# power_control.net
KiCad netlist of a schematic drawn in EAGLE
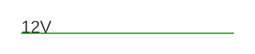
[diagram p0: schematic, sheet 1]
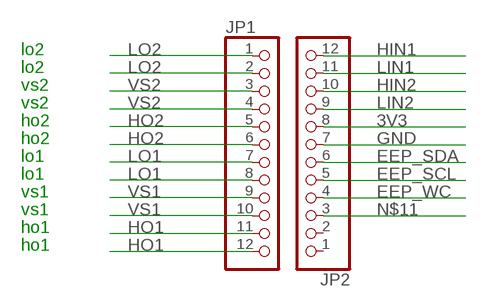
[diagram p1: schematic, sheet 2]
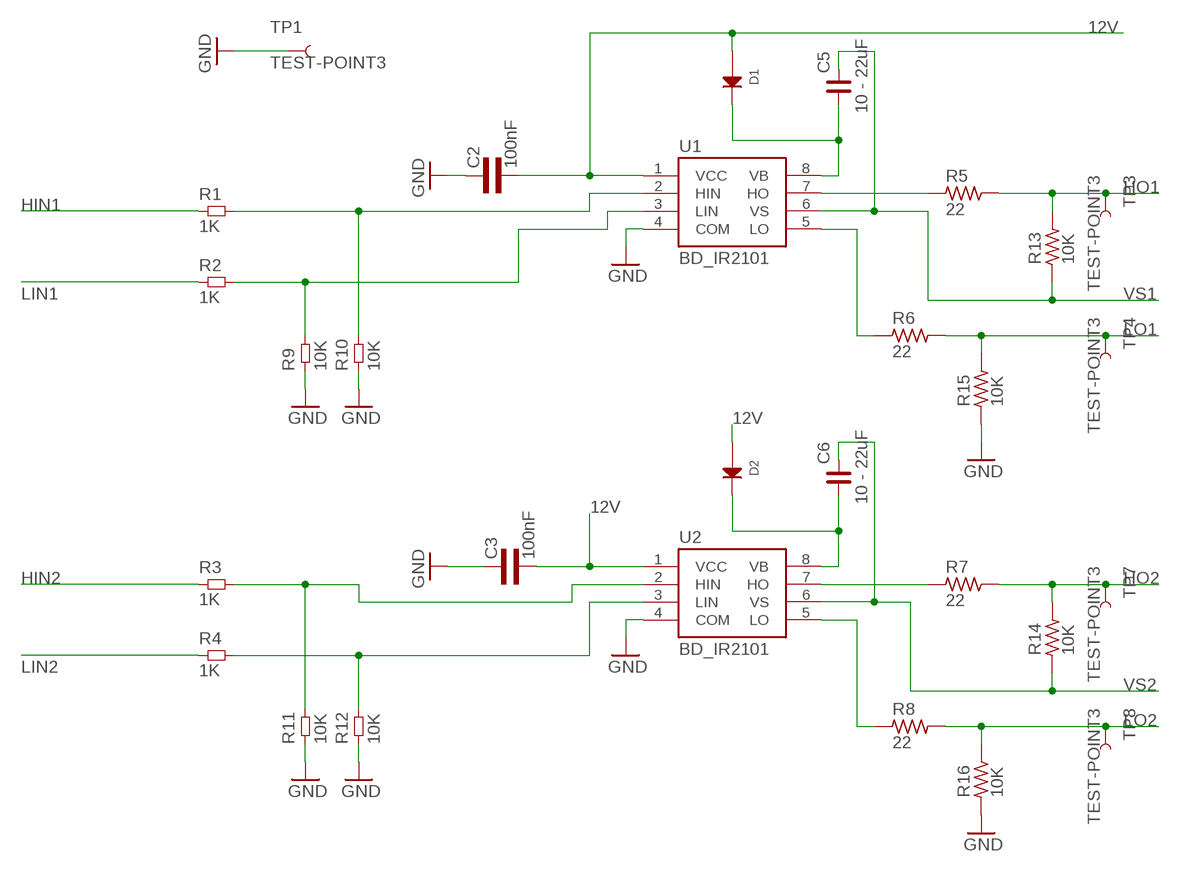
[diagram p2: schematic, sheet 3]
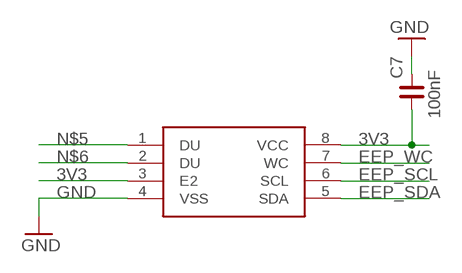
[diagram p3: schematic, sheet 4]
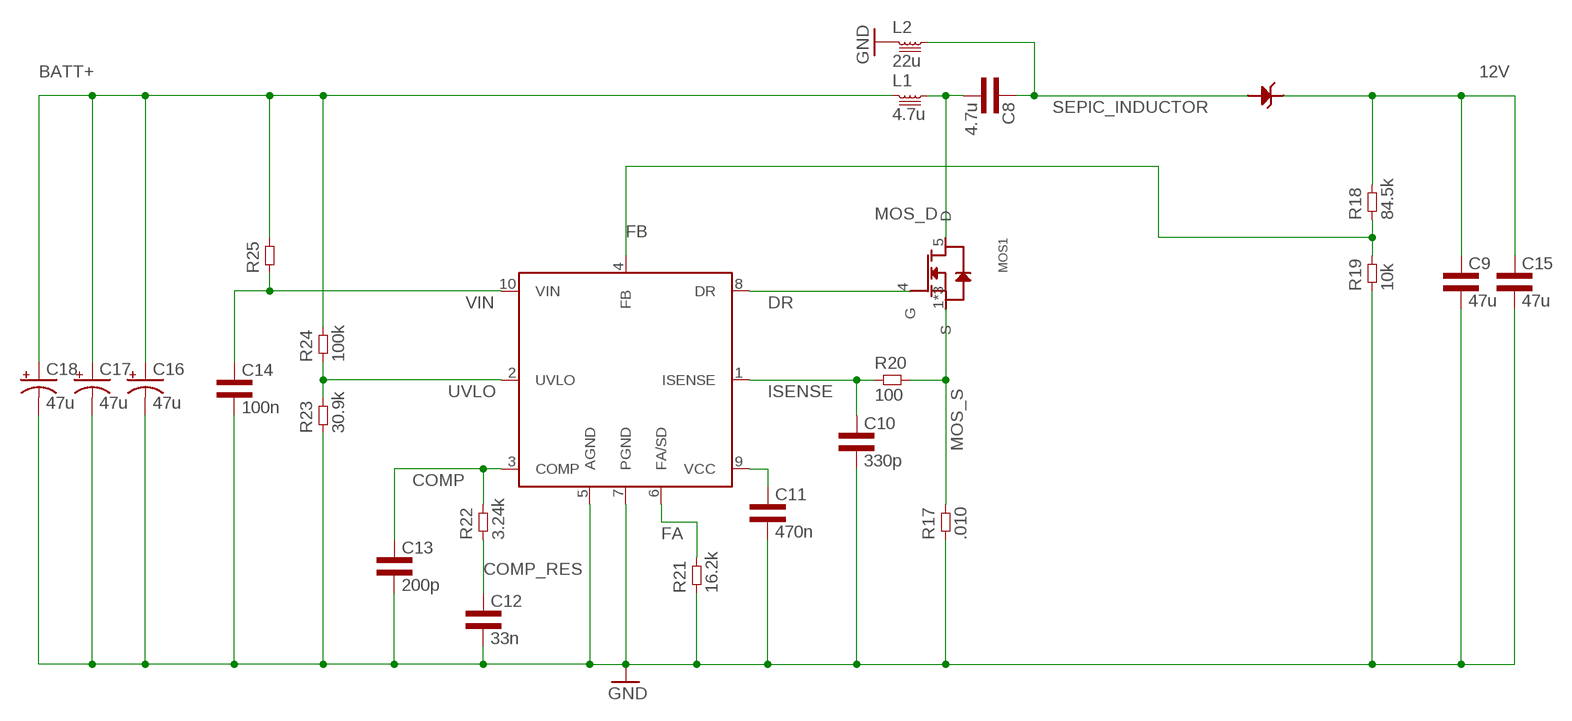
[diagram p4: schematic, sheet 5]

(export (version "E")
  (design (tool "Eeschema 10.0.6"))
  (components
    (comp (ref "JP1")
      (value "PINHD-1X12_2.54-SMD")
      (footprint "eagle-import:1X12SMD")
      (libsource (lib "eagle-import") (part "PINHD-1X12_2.54-SMD"))
    )
    (comp (ref "JP2")
      (value "PINHD-1X12_2.54-SMD")
      (footprint "eagle-import:1X12SMD")
      (libsource (lib "eagle-import") (part "PINHD-1X12_2.54-SMD"))
    )
    (comp (ref "C2")
      (value "100nF")
      (footprint "eagle-import:0603L3")
      (libsource (lib "eagle-import") (part "CAP0603L3"))
    )
    (comp (ref "C3")
      (value "100nF")
      (footprint "eagle-import:0603L3")
      (libsource (lib "eagle-import") (part "CAP0603L3"))
    )
    (comp (ref "C5")
      (value "10 - 22uF")
      (footprint "eagle-import:C0805")
      (libsource (lib "eagle-import") (part "C_0805"))
    )
    (comp (ref "C6")
      (value "10 - 22uF")
      (footprint "eagle-import:C0805")
      (libsource (lib "eagle-import") (part "C_0805"))
    )
    (comp (ref "D1")
      (value "DIODETMINIP2-F2-B")
      (footprint "eagle-import:TMINIP2-F2-B")
      (fields (field (name "PARTNUM") "DB2441600L"))
      (libsource (lib "eagle-import") (part "DIODETMINIP2-F2-B"))
    )
    (comp (ref "D2")
      (value "DIODETMINIP2-F2-B")
      (footprint "eagle-import:TMINIP2-F2-B")
      (fields (field (name "PARTNUM") "DB2441600L"))
      (libsource (lib "eagle-import") (part "DIODETMINIP2-F2-B"))
    )
    (comp (ref "R1")
      (value "1K")
      (footprint "eagle-import:0603L3")
      (libsource (lib "eagle-import") (part "RES0603L3"))
    )
    (comp (ref "R2")
      (value "1K")
      (footprint "eagle-import:0603L3")
      (libsource (lib "eagle-import") (part "RES0603L3"))
    )
    (comp (ref "R3")
      (value "1K")
      (footprint "eagle-import:0603L3")
      (libsource (lib "eagle-import") (part "RES0603L3"))
    )
    (comp (ref "R4")
      (value "1K")
      (footprint "eagle-import:0603L3")
      (libsource (lib "eagle-import") (part "RES0603L3"))
    )
    (comp (ref "R5")
      (value "22")
      (footprint "eagle-import:R0805")
      (libsource (lib "eagle-import") (part "R_0805"))
    )
    (comp (ref "R6")
      (value "22")
      (footprint "eagle-import:R0805")
      (libsource (lib "eagle-import") (part "R_0805"))
    )
    (comp (ref "R7")
      (value "22")
      (footprint "eagle-import:R0805")
      (libsource (lib "eagle-import") (part "R_0805"))
    )
    (comp (ref "R8")
      (value "22")
      (footprint "eagle-import:R0805")
      (libsource (lib "eagle-import") (part "R_0805"))
    )
    (comp (ref "R9")
      (value "10K")
      (footprint "eagle-import:0603L3")
      (libsource (lib "eagle-import") (part "RES0603L3"))
    )
    (comp (ref "R10")
      (value "10K")
      (footprint "eagle-import:0603L3")
      (libsource (lib "eagle-import") (part "RES0603L3"))
    )
    (comp (ref "R11")
      (value "10K")
      (footprint "eagle-import:0603L3")
      (libsource (lib "eagle-import") (part "RES0603L3"))
    )
    (comp (ref "R12")
      (value "10K")
      (footprint "eagle-import:0603L3")
      (libsource (lib "eagle-import") (part "RES0603L3"))
    )
    (comp (ref "R13")
      (value "10K")
      (footprint "eagle-import:R0805")
      (libsource (lib "eagle-import") (part "R_0805"))
    )
    (comp (ref "R14")
      (value "10K")
      (footprint "eagle-import:R0805")
      (libsource (lib "eagle-import") (part "R_0805"))
    )
    (comp (ref "R15")
      (value "10K")
      (footprint "eagle-import:R0805")
      (libsource (lib "eagle-import") (part "R_0805"))
    )
    (comp (ref "R16")
      (value "10K")
      (footprint "eagle-import:R0805")
      (libsource (lib "eagle-import") (part "R_0805"))
    )
    (comp (ref "TP1")
      (value "TEST-POINT3")
      (footprint "eagle-import:PAD.03X.03")
      (libsource (lib "eagle-import") (part "TEST-POINT3"))
    )
    (comp (ref "TP3")
      (value "TEST-POINT3")
      (footprint "eagle-import:PAD.03X.03")
      (libsource (lib "eagle-import") (part "TEST-POINT3"))
    )
    (comp (ref "TP4")
      (value "TEST-POINT3")
      (footprint "eagle-import:PAD.03X.03")
      (libsource (lib "eagle-import") (part "TEST-POINT3"))
    )
    (comp (ref "TP7")
      (value "TEST-POINT3")
      (footprint "eagle-import:PAD.03X.03")
      (libsource (lib "eagle-import") (part "TEST-POINT3"))
    )
    (comp (ref "TP8")
      (value "TEST-POINT3")
      (footprint "eagle-import:PAD.03X.03")
      (libsource (lib "eagle-import") (part "TEST-POINT3"))
    )
    (comp (ref "U1")
      (value "BD_IR2101")
      (footprint "eagle-import:SO8")
      (libsource (lib "eagle-import") (part "BD_IR2101"))
    )
    (comp (ref "U2")
      (value "BD_IR2101")
      (footprint "eagle-import:SO8")
      (libsource (lib "eagle-import") (part "BD_IR2101"))
    )
    (comp (ref "C8")
      (value "4.7u")
      (footprint "eagle-import:1206L3")
      (libsource (lib "eagle-import") (part "CAP1206L3"))
    )
    (comp (ref "C9")
      (value "47u")
      (footprint "eagle-import:1210L3")
      (libsource (lib "eagle-import") (part "CAP1210L3"))
    )
    (comp (ref "C10")
      (value "330p")
      (footprint "eagle-import:0402L3")
      (libsource (lib "eagle-import") (part "CAP0402L3"))
    )
    (comp (ref "C11")
      (value "470n")
      (footprint "eagle-import:0402L3")
      (libsource (lib "eagle-import") (part "CAP0402L3"))
    )
    (comp (ref "C12")
      (value "33n")
      (footprint "eagle-import:0402L3")
      (libsource (lib "eagle-import") (part "CAP0402L3"))
    )
    (comp (ref "C13")
      (value "200p")
      (footprint "eagle-import:0402L3")
      (libsource (lib "eagle-import") (part "CAP0402L3"))
    )
    (comp (ref "C14")
      (value "100n")
      (footprint "eagle-import:0603L3")
      (libsource (lib "eagle-import") (part "CAP0603L3"))
    )
    (comp (ref "C15")
      (value "47u")
      (footprint "eagle-import:1210L3")
      (libsource (lib "eagle-import") (part "CAP1210L3"))
    )
    (comp (ref "C16")
      (value "47u")
      (footprint "eagle-import:CT7343")
      (libsource (lib "eagle-import") (part "CPOL-USCT7343"))
    )
    (comp (ref "C17")
      (value "47u")
      (footprint "eagle-import:CT7343")
      (libsource (lib "eagle-import") (part "CPOL-USCT7343"))
    )
    (comp (ref "C18")
      (value "47u")
      (footprint "eagle-import:CT7343")
      (libsource (lib "eagle-import") (part "CPOL-USCT7343"))
    )
    (comp (ref "D3")
      (value "SCHOTTKYDIODEDPAK")
      (footprint "eagle-import:DPAK")
      (libsource (lib "eagle-import") (part "SCHOTTKYDIODEDPAK"))
    )
    (comp (ref "L1")
      (value "4.7u")
      (footprint "eagle-import:SRP6540")
      (libsource (lib "eagle-import") (part "INDUCTORSRP6540"))
    )
    (comp (ref "L2")
      (value "22u")
      (footprint "eagle-import:IHLP3232DZ11")
      (libsource (lib "eagle-import") (part "INDUCTORIHLP3232DZ11"))
    )
    (comp (ref "MOS1")
      (value "MOSFET-NPG-TDSON-8")
      (footprint "eagle-import:PG-TDSON-8")
      (libsource (lib "eagle-import") (part "MOSFET-NPG-TDSON-8"))
    )
    (comp (ref "R17")
      (value ".010")
      (footprint "eagle-import:1206L3")
      (libsource (lib "eagle-import") (part "RES1206L3"))
    )
    (comp (ref "R18")
      (value "84.5k")
      (footprint "eagle-import:0402L3")
      (libsource (lib "eagle-import") (part "RES0402L3"))
    )
    (comp (ref "R19")
      (value "10k")
      (footprint "eagle-import:0402L3")
      (libsource (lib "eagle-import") (part "RES0402L3"))
    )
    (comp (ref "R20")
      (value "100")
      (footprint "eagle-import:0402L3")
      (libsource (lib "eagle-import") (part "RES0402L3"))
    )
    (comp (ref "R21")
      (value "16.2k")
      (footprint "eagle-import:0402L3")
      (libsource (lib "eagle-import") (part "RES0402L3"))
    )
    (comp (ref "R22")
      (value "3.24k")
      (footprint "eagle-import:0402L3")
      (libsource (lib "eagle-import") (part "RES0402L3"))
    )
    (comp (ref "R23")
      (value "30.9k")
      (footprint "eagle-import:0402L3")
      (libsource (lib "eagle-import") (part "RES0402L3"))
    )
    (comp (ref "R24")
      (value "100k")
      (footprint "eagle-import:0402L3")
      (libsource (lib "eagle-import") (part "RES0402L3"))
    )
    (comp (ref "R25")
      (value "RES0402L3")
      (footprint "eagle-import:0402L3")
      (libsource (lib "eagle-import") (part "RES0402L3"))
    )
    (comp (ref "U3")
      (value "LM3481")
      (footprint "eagle-import:S-PDSO-G10")
      (libsource (lib "eagle-import") (part "LM3481"))
    )
    (comp (ref "C7")
      (value "100nF")
      (footprint "eagle-import:C0201")
      (libsource (lib "eagle-import") (part "C_0201"))
    )
    (comp (ref "M24M02")
      (value "M24M02-DRMN6TP")
      (footprint "eagle-import:SO08")
      (libsource (lib "eagle-import") (part "M24M02-DRMN6TP"))
    )
  )
  (nets
    (net (code "1") (name "3V3") (class "Default")
      (node (ref "C7") (pin "1") (pinfunction "1_1") (pintype "passive"))
      (node (ref "JP2") (pin "8") (pinfunction "8_8") (pintype "passive"))
      (node (ref "M24M02") (pin "3") (pinfunction "E2_3") (pintype "bidirectional"))
      (node (ref "M24M02") (pin "8") (pinfunction "VCC_8") (pintype "bidirectional"))
    )
    (net (code "2") (name "12V") (class "Default")
      (node (ref "C15") (pin "P$1") (pinfunction "1_P$1") (pintype "bidirectional"))
      (node (ref "C2") (pin "P$2") (pinfunction "2_P$2") (pintype "bidirectional"))
      (node (ref "C3") (pin "P$2") (pinfunction "2_P$2") (pintype "bidirectional"))
      (node (ref "C9") (pin "P$1") (pinfunction "1_P$1") (pintype "bidirectional"))
      (node (ref "D1") (pin "2") (pinfunction "ANODE_2") (pintype "bidirectional"))
      (node (ref "D2") (pin "2") (pinfunction "ANODE_2") (pintype "bidirectional"))
      (node (ref "D3") (pin "TAB") (pinfunction "CATHODE_TAB") (pintype "bidirectional"))
      (node (ref "R18") (pin "P$2") (pinfunction "2_P$2") (pintype "bidirectional"))
      (node (ref "U1") (pin "1") (pinfunction "VCC_1") (pintype "bidirectional"))
      (node (ref "U2") (pin "1") (pinfunction "VCC_1") (pintype "bidirectional"))
    )
    (net (code "3") (name "BATT+") (class "Default")
      (node (ref "C16") (pin "+") (pinfunction "+_+") (pintype "passive"))
      (node (ref "C17") (pin "+") (pinfunction "+_+") (pintype "passive"))
      (node (ref "C18") (pin "+") (pinfunction "+_+") (pintype "passive"))
      (node (ref "L1") (pin "1") (pinfunction "1_1") (pintype "bidirectional"))
      (node (ref "R24") (pin "P$2") (pinfunction "2_P$2") (pintype "bidirectional"))
      (node (ref "R25") (pin "P$2") (pinfunction "2_P$2") (pintype "bidirectional"))
    )
    (net (code "4") (name "COMP") (class "Default")
      (node (ref "C13") (pin "P$1") (pinfunction "1_P$1") (pintype "bidirectional"))
      (node (ref "R22") (pin "P$2") (pinfunction "2_P$2") (pintype "bidirectional"))
      (node (ref "U3") (pin "3") (pinfunction "COMP_3") (pintype "bidirectional"))
    )
    (net (code "5") (name "COMP_RES") (class "Default")
      (node (ref "C12") (pin "P$1") (pinfunction "1_P$1") (pintype "bidirectional"))
      (node (ref "R22") (pin "P$1") (pinfunction "1_P$1") (pintype "bidirectional"))
    )
    (net (code "6") (name "DR") (class "Default")
      (node (ref "MOS1") (pin "4") (pinfunction "G_4") (pintype "bidirectional"))
      (node (ref "U3") (pin "8") (pinfunction "DR_8") (pintype "bidirectional"))
    )
    (net (code "7") (name "EEP_SCL") (class "Default")
      (node (ref "JP2") (pin "5") (pinfunction "5_5") (pintype "passive"))
      (node (ref "M24M02") (pin "6") (pinfunction "SCL_6") (pintype "bidirectional"))
    )
    (net (code "8") (name "EEP_SDA") (class "Default")
      (node (ref "JP2") (pin "6") (pinfunction "6_6") (pintype "passive"))
      (node (ref "M24M02") (pin "5") (pinfunction "SDA_5") (pintype "bidirectional"))
    )
    (net (code "9") (name "EEP_WC") (class "Default")
      (node (ref "JP2") (pin "4") (pinfunction "4_4") (pintype "passive"))
      (node (ref "M24M02") (pin "7") (pinfunction "WC_7") (pintype "bidirectional"))
    )
    (net (code "10") (name "FA") (class "Default")
      (node (ref "R21") (pin "P$2") (pinfunction "2_P$2") (pintype "bidirectional"))
      (node (ref "U3") (pin "6") (pinfunction "FA/SD_6") (pintype "bidirectional"))
    )
    (net (code "11") (name "FB") (class "Default")
      (node (ref "R18") (pin "P$1") (pinfunction "1_P$1") (pintype "bidirectional"))
      (node (ref "R19") (pin "P$2") (pinfunction "2_P$2") (pintype "bidirectional"))
      (node (ref "U3") (pin "4") (pinfunction "FB_4") (pintype "bidirectional"))
    )
    (net (code "12") (name "GND") (class "Default")
      (node (ref "C10") (pin "P$2") (pinfunction "2_P$2") (pintype "bidirectional"))
      (node (ref "C11") (pin "P$2") (pinfunction "2_P$2") (pintype "bidirectional"))
      (node (ref "C12") (pin "P$2") (pinfunction "2_P$2") (pintype "bidirectional"))
      (node (ref "C13") (pin "P$2") (pinfunction "2_P$2") (pintype "bidirectional"))
      (node (ref "C14") (pin "P$2") (pinfunction "2_P$2") (pintype "bidirectional"))
      (node (ref "C15") (pin "P$2") (pinfunction "2_P$2") (pintype "bidirectional"))
      (node (ref "C16") (pin "-") (pinfunction "-_-") (pintype "passive"))
      (node (ref "C17") (pin "-") (pinfunction "-_-") (pintype "passive"))
      (node (ref "C18") (pin "-") (pinfunction "-_-") (pintype "passive"))
      (node (ref "C2") (pin "P$1") (pinfunction "1_P$1") (pintype "bidirectional"))
      (node (ref "C3") (pin "P$1") (pinfunction "1_P$1") (pintype "bidirectional"))
      (node (ref "C7") (pin "2") (pinfunction "2_2") (pintype "passive"))
      (node (ref "C9") (pin "P$2") (pinfunction "2_P$2") (pintype "bidirectional"))
      (node (ref "JP2") (pin "7") (pinfunction "7_7") (pintype "passive"))
      (node (ref "L2") (pin "1") (pinfunction "1_1") (pintype "bidirectional"))
      (node (ref "M24M02") (pin "4") (pinfunction "VSS_4") (pintype "bidirectional"))
      (node (ref "R10") (pin "P$1") (pinfunction "1_P$1") (pintype "bidirectional"))
      (node (ref "R11") (pin "P$1") (pinfunction "1_P$1") (pintype "bidirectional"))
      (node (ref "R12") (pin "P$1") (pinfunction "1_P$1") (pintype "bidirectional"))
      (node (ref "R15") (pin "1") (pinfunction "1_1") (pintype "passive"))
      (node (ref "R16") (pin "1") (pinfunction "1_1") (pintype "passive"))
      (node (ref "R17") (pin "1") (pinfunction "1_1") (pintype "bidirectional"))
      (node (ref "R19") (pin "P$1") (pinfunction "1_P$1") (pintype "bidirectional"))
      (node (ref "R21") (pin "P$1") (pinfunction "1_P$1") (pintype "bidirectional"))
      (node (ref "R23") (pin "P$1") (pinfunction "1_P$1") (pintype "bidirectional"))
      (node (ref "R9") (pin "P$1") (pinfunction "1_P$1") (pintype "bidirectional"))
      (node (ref "TP1") (pin "P$1") (pinfunction "1_P$1") (pintype "bidirectional"))
      (node (ref "U1") (pin "4") (pinfunction "COM_4") (pintype "bidirectional"))
      (node (ref "U2") (pin "4") (pinfunction "COM_4") (pintype "bidirectional"))
      (node (ref "U3") (pin "5") (pinfunction "AGND_5") (pintype "bidirectional"))
      (node (ref "U3") (pin "7") (pinfunction "PGND_7") (pintype "bidirectional"))
    )
    (net (code "13") (name "HIN1") (class "Default")
      (node (ref "JP2") (pin "12") (pinfunction "12_12") (pintype "passive"))
      (node (ref "R1") (pin "P$1") (pinfunction "1_P$1") (pintype "bidirectional"))
    )
    (net (code "14") (name "HIN2") (class "Default")
      (node (ref "JP2") (pin "10") (pinfunction "10_10") (pintype "passive"))
      (node (ref "R3") (pin "P$1") (pinfunction "1_P$1") (pintype "bidirectional"))
    )
    (net (code "15") (name "HO1") (class "Default")
      (node (ref "JP1") (pin "11") (pinfunction "11_11") (pintype "passive"))
      (node (ref "JP1") (pin "12") (pinfunction "12_12") (pintype "passive"))
      (node (ref "R13") (pin "2") (pinfunction "2_2") (pintype "passive"))
      (node (ref "R5") (pin "2") (pinfunction "2_2") (pintype "passive"))
      (node (ref "TP3") (pin "P$1") (pinfunction "1_P$1") (pintype "bidirectional"))
    )
    (net (code "16") (name "HO2") (class "Default")
      (node (ref "JP1") (pin "5") (pinfunction "5_5") (pintype "passive"))
      (node (ref "JP1") (pin "6") (pinfunction "6_6") (pintype "passive"))
      (node (ref "R14") (pin "2") (pinfunction "2_2") (pintype "passive"))
      (node (ref "R7") (pin "2") (pinfunction "2_2") (pintype "passive"))
      (node (ref "TP7") (pin "P$1") (pinfunction "1_P$1") (pintype "bidirectional"))
    )
    (net (code "17") (name "ISENSE") (class "Default")
      (node (ref "C10") (pin "P$1") (pinfunction "1_P$1") (pintype "bidirectional"))
      (node (ref "R20") (pin "P$1") (pinfunction "1_P$1") (pintype "bidirectional"))
      (node (ref "U3") (pin "1") (pinfunction "ISENSE_1") (pintype "bidirectional"))
    )
    (net (code "18") (name "LIN1") (class "Default")
      (node (ref "JP2") (pin "11") (pinfunction "11_11") (pintype "passive"))
      (node (ref "R2") (pin "P$1") (pinfunction "1_P$1") (pintype "bidirectional"))
    )
    (net (code "19") (name "LIN2") (class "Default")
      (node (ref "JP2") (pin "9") (pinfunction "9_9") (pintype "passive"))
      (node (ref "R4") (pin "P$1") (pinfunction "1_P$1") (pintype "bidirectional"))
    )
    (net (code "20") (name "LO1") (class "Default")
      (node (ref "JP1") (pin "7") (pinfunction "7_7") (pintype "passive"))
      (node (ref "JP1") (pin "8") (pinfunction "8_8") (pintype "passive"))
      (node (ref "R15") (pin "2") (pinfunction "2_2") (pintype "passive"))
      (node (ref "R6") (pin "2") (pinfunction "2_2") (pintype "passive"))
      (node (ref "TP4") (pin "P$1") (pinfunction "1_P$1") (pintype "bidirectional"))
    )
    (net (code "21") (name "LO2") (class "Default")
      (node (ref "JP1") (pin "1") (pinfunction "1_1") (pintype "passive"))
      (node (ref "JP1") (pin "2") (pinfunction "2_2") (pintype "passive"))
      (node (ref "R16") (pin "2") (pinfunction "2_2") (pintype "passive"))
      (node (ref "R8") (pin "2") (pinfunction "2_2") (pintype "passive"))
      (node (ref "TP8") (pin "P$1") (pinfunction "1_P$1") (pintype "bidirectional"))
    )
    (net (code "22") (name "MOS_D") (class "Default")
      (node (ref "C8") (pin "2") (pinfunction "2_2") (pintype "bidirectional"))
      (node (ref "L1") (pin "2") (pinfunction "2_2") (pintype "bidirectional"))
      (node (ref "MOS1") (pin "5") (pinfunction "D_5") (pintype "bidirectional"))
    )
    (net (code "23") (name "MOS_S") (class "Default")
      (node (ref "MOS1") (pin "1") (pinfunction "S_1") (pintype "bidirectional"))
      (node (ref "MOS1") (pin "2") (pinfunction "S_2") (pintype "bidirectional"))
      (node (ref "MOS1") (pin "3") (pinfunction "S_3") (pintype "bidirectional"))
      (node (ref "R17") (pin "2") (pinfunction "2_2") (pintype "bidirectional"))
      (node (ref "R20") (pin "P$2") (pinfunction "2_P$2") (pintype "bidirectional"))
    )
    (net (code "24") (name "N$5") (class "Default")
      (node (ref "M24M02") (pin "1") (pinfunction "DU_1") (pintype "bidirectional"))
    )
    (net (code "25") (name "N$6") (class "Default")
      (node (ref "M24M02") (pin "2") (pinfunction "DU_2") (pintype "bidirectional"))
    )
    (net (code "26") (name "N$11") (class "Default")
      (node (ref "JP2") (pin "3") (pinfunction "3_3") (pintype "passive"))
    )
    (net (code "27") (name "Net-(C11-1)") (class "Default")
      (node (ref "C11") (pin "P$1") (pinfunction "1_P$1") (pintype "bidirectional"))
      (node (ref "U3") (pin "9") (pinfunction "VCC_9") (pintype "bidirectional"))
    )
    (net (code "28") (name "Net-(D1-CATHODE)") (class "Default")
      (node (ref "C5") (pin "1") (pinfunction "1_1") (pintype "passive"))
      (node (ref "D1") (pin "1") (pinfunction "CATHODE_1") (pintype "bidirectional"))
      (node (ref "U1") (pin "8") (pinfunction "VB_8") (pintype "bidirectional"))
    )
    (net (code "29") (name "Net-(D2-CATHODE)") (class "Default")
      (node (ref "C6") (pin "1") (pinfunction "1_1") (pintype "passive"))
      (node (ref "D2") (pin "1") (pinfunction "CATHODE_1") (pintype "bidirectional"))
      (node (ref "U2") (pin "8") (pinfunction "VB_8") (pintype "bidirectional"))
    )
    (net (code "30") (name "Net-(R1-2)") (class "Default")
      (node (ref "R1") (pin "P$2") (pinfunction "2_P$2") (pintype "bidirectional"))
      (node (ref "R10") (pin "P$2") (pinfunction "2_P$2") (pintype "bidirectional"))
      (node (ref "U1") (pin "2") (pinfunction "HIN_2") (pintype "bidirectional"))
    )
    (net (code "31") (name "Net-(R2-2)") (class "Default")
      (node (ref "R2") (pin "P$2") (pinfunction "2_P$2") (pintype "bidirectional"))
      (node (ref "R9") (pin "P$2") (pinfunction "2_P$2") (pintype "bidirectional"))
      (node (ref "U1") (pin "3") (pinfunction "LIN_3") (pintype "bidirectional"))
    )
    (net (code "32") (name "Net-(R11-2)") (class "Default")
      (node (ref "R11") (pin "P$2") (pinfunction "2_P$2") (pintype "bidirectional"))
      (node (ref "R3") (pin "P$2") (pinfunction "2_P$2") (pintype "bidirectional"))
      (node (ref "U2") (pin "2") (pinfunction "HIN_2") (pintype "bidirectional"))
    )
    (net (code "33") (name "Net-(R12-2)") (class "Default")
      (node (ref "R12") (pin "P$2") (pinfunction "2_P$2") (pintype "bidirectional"))
      (node (ref "R4") (pin "P$2") (pinfunction "2_P$2") (pintype "bidirectional"))
      (node (ref "U2") (pin "3") (pinfunction "LIN_3") (pintype "bidirectional"))
    )
    (net (code "34") (name "Net-(U1-HO)") (class "Default")
      (node (ref "R5") (pin "1") (pinfunction "1_1") (pintype "passive"))
      (node (ref "U1") (pin "7") (pinfunction "HO_7") (pintype "bidirectional"))
    )
    (net (code "35") (name "Net-(U1-LO)") (class "Default")
      (node (ref "R6") (pin "1") (pinfunction "1_1") (pintype "passive"))
      (node (ref "U1") (pin "5") (pinfunction "LO_5") (pintype "bidirectional"))
    )
    (net (code "36") (name "Net-(U2-HO)") (class "Default")
      (node (ref "R7") (pin "1") (pinfunction "1_1") (pintype "passive"))
      (node (ref "U2") (pin "7") (pinfunction "HO_7") (pintype "bidirectional"))
    )
    (net (code "37") (name "Net-(U2-LO)") (class "Default")
      (node (ref "R8") (pin "1") (pinfunction "1_1") (pintype "passive"))
      (node (ref "U2") (pin "5") (pinfunction "LO_5") (pintype "bidirectional"))
    )
    (net (code "38") (name "SEPIC_INDUCTOR") (class "Default")
      (node (ref "C8") (pin "1") (pinfunction "1_1") (pintype "bidirectional"))
      (node (ref "D3") (pin "1") (pinfunction "ANODE_1") (pintype "bidirectional"))
      (node (ref "D3") (pin "3") (pinfunction "ANODE_3") (pintype "bidirectional"))
      (node (ref "L2") (pin "2") (pinfunction "2_2") (pintype "bidirectional"))
    )
    (net (code "39") (name "UVLO") (class "Default")
      (node (ref "R23") (pin "P$2") (pinfunction "2_P$2") (pintype "bidirectional"))
      (node (ref "R24") (pin "P$1") (pinfunction "1_P$1") (pintype "bidirectional"))
      (node (ref "U3") (pin "2") (pinfunction "UVLO_2") (pintype "bidirectional"))
    )
    (net (code "40") (name "VIN") (class "Default")
      (node (ref "C14") (pin "P$1") (pinfunction "1_P$1") (pintype "bidirectional"))
      (node (ref "R25") (pin "P$1") (pinfunction "1_P$1") (pintype "bidirectional"))
      (node (ref "U3") (pin "10") (pinfunction "VIN_10") (pintype "bidirectional"))
    )
    (net (code "41") (name "VS1") (class "Default")
      (node (ref "C5") (pin "2") (pinfunction "2_2") (pintype "passive"))
      (node (ref "JP1") (pin "10") (pinfunction "10_10") (pintype "passive"))
      (node (ref "JP1") (pin "9") (pinfunction "9_9") (pintype "passive"))
      (node (ref "R13") (pin "1") (pinfunction "1_1") (pintype "passive"))
      (node (ref "U1") (pin "6") (pinfunction "VS_6") (pintype "bidirectional"))
    )
    (net (code "42") (name "VS2") (class "Default")
      (node (ref "C6") (pin "2") (pinfunction "2_2") (pintype "passive"))
      (node (ref "JP1") (pin "3") (pinfunction "3_3") (pintype "passive"))
      (node (ref "JP1") (pin "4") (pinfunction "4_4") (pintype "passive"))
      (node (ref "R14") (pin "1") (pinfunction "1_1") (pintype "passive"))
      (node (ref "U2") (pin "6") (pinfunction "VS_6") (pintype "bidirectional"))
    )
    (net (code "43") (name "unconnected-(JP2-Pad1)") (class "Default")
      (node (ref "JP2") (pin "1") (pinfunction "1_1") (pintype "passive"))
    )
    (net (code "44") (name "unconnected-(JP2-Pad2)") (class "Default")
      (node (ref "JP2") (pin "2") (pinfunction "2_2") (pintype "passive"))
    )
  )
)
